# Main.net
KiCad netlist of a schematic drawn in Altium Designer
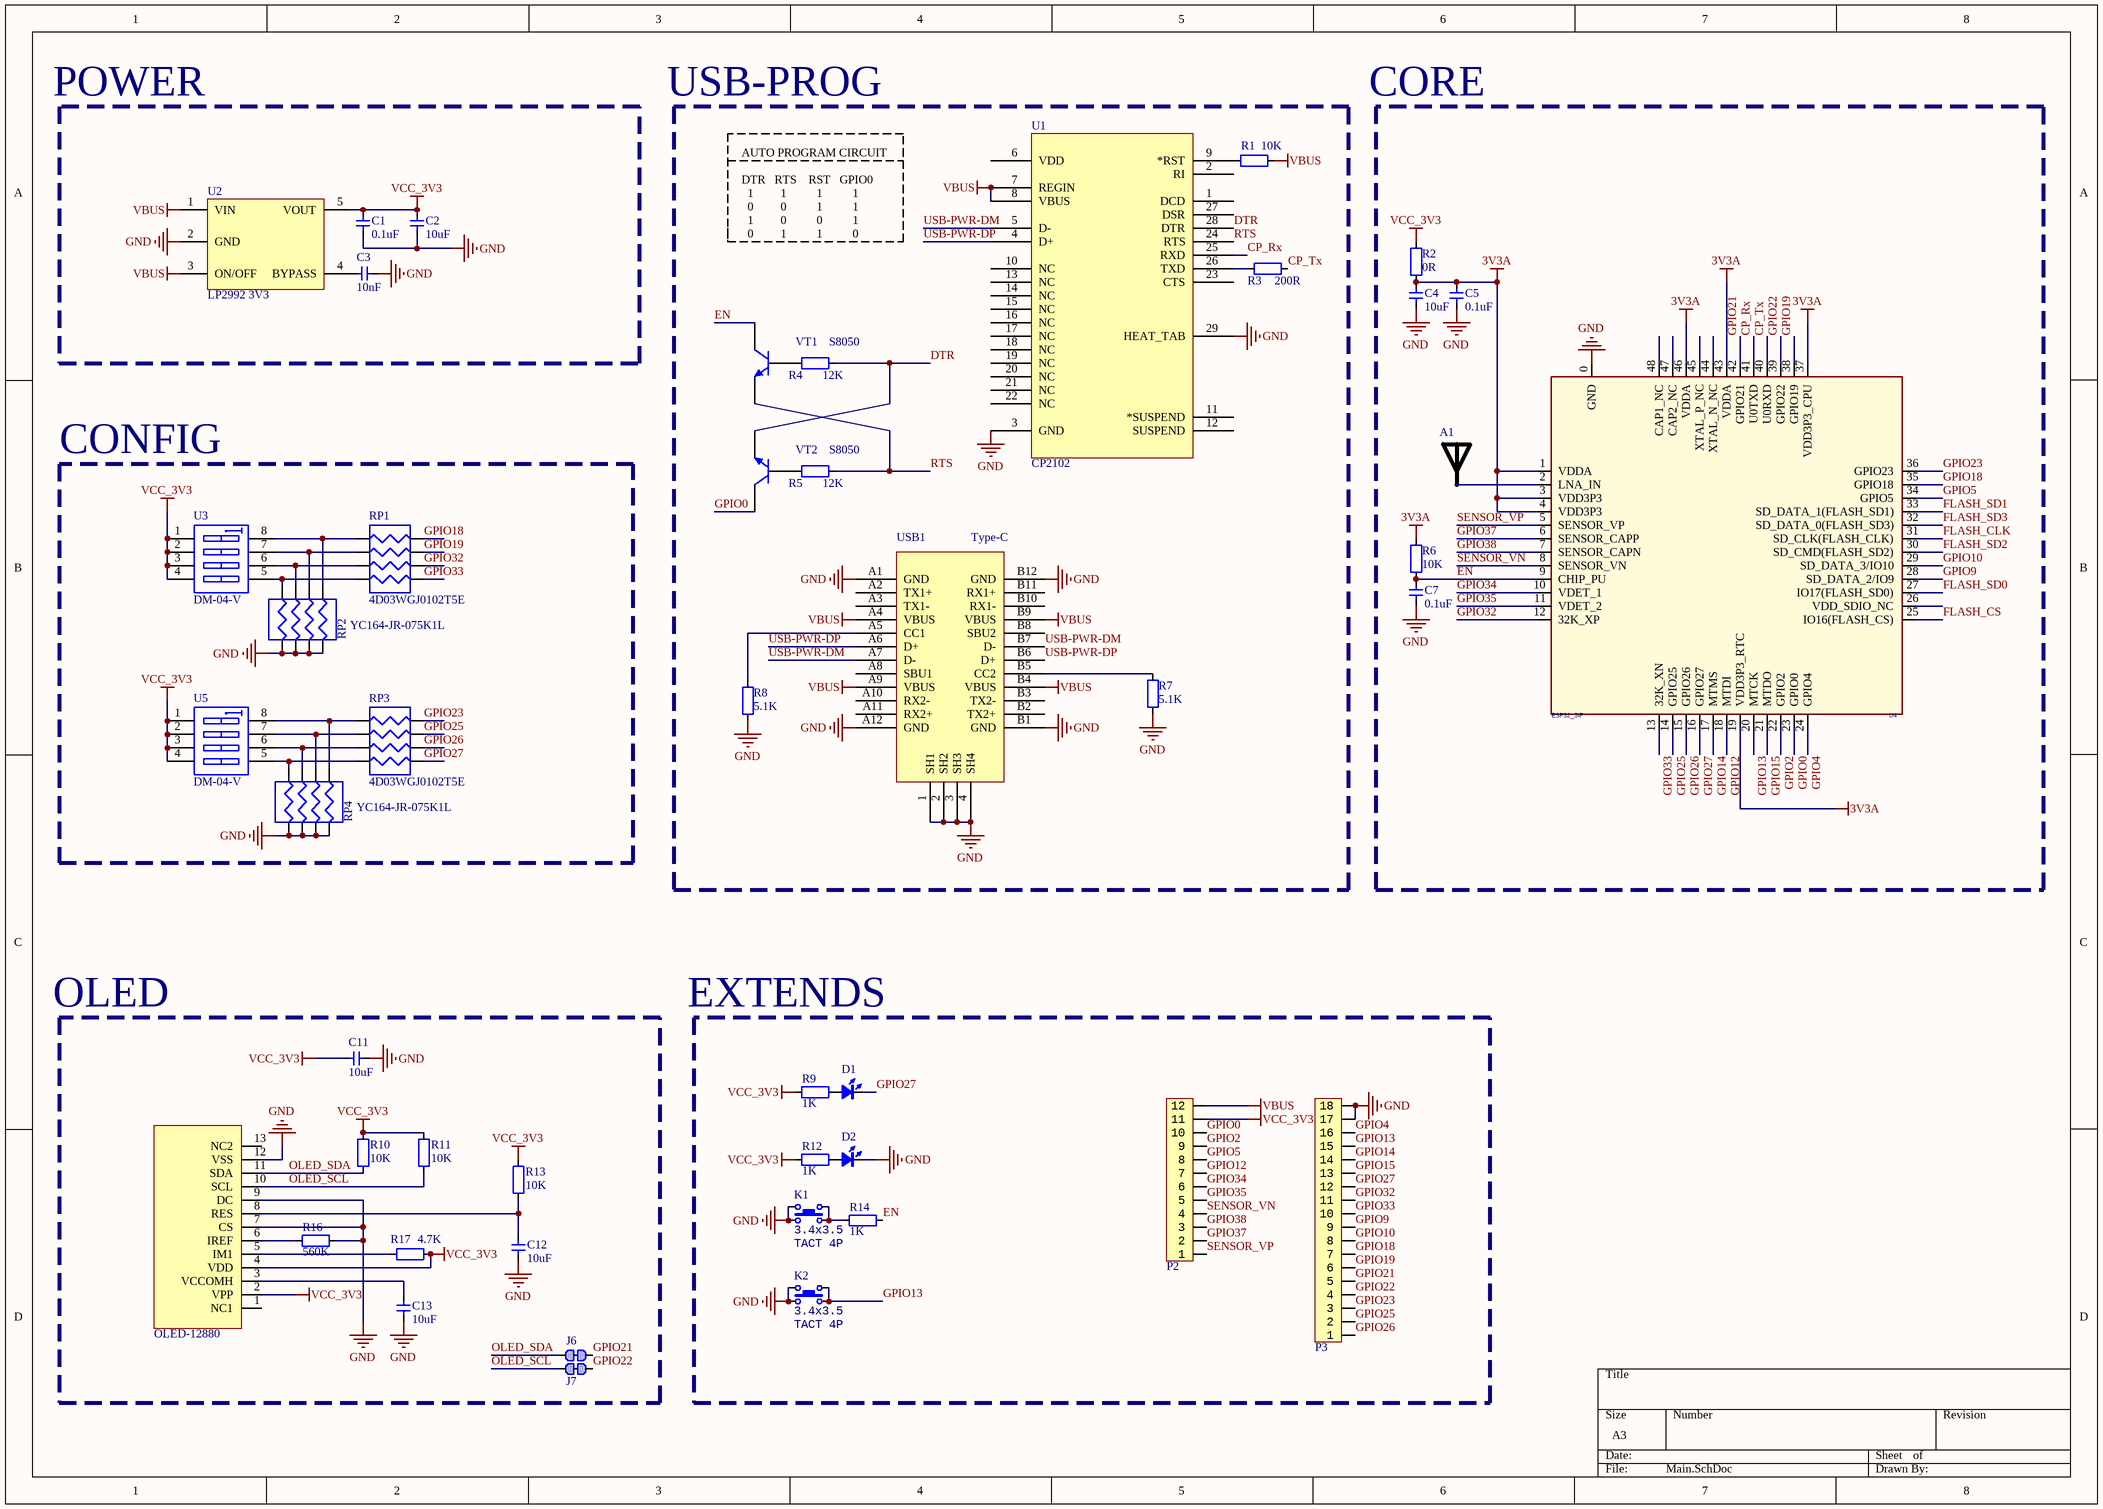
[diagram p0: Main.SchDoc]

(export (version "E")
  (design (tool "Eeschema 10.0.6"))
  (components
    (comp (ref "1")
      (value "OLED-12880")
      (footprint "OLED-12880")
      (libsource (lib "mLib") (part "OLED-12880"))
    )
    (comp (ref "A1")
      (value "RAINSUN")
      (footprint "ANT-Rainsun-AN5120")
      (libsource (lib "MyPcbLib") (part "ANT-Rainsun-AP5120"))
    )
    (comp (ref "C1")
      (value "0.1uF")
      (footprint "CAP_0402")
      (description "Capacitor")
      (libsource (lib "MyPcbLib") (part "电容-0402"))
    )
    (comp (ref "C2")
      (value "10uF")
      (footprint "CAP_0402")
      (description "Capacitor")
      (libsource (lib "MyPcbLib") (part "电容-0402"))
    )
    (comp (ref "C3")
      (value "10nF")
      (footprint "CAP_0402")
      (description "Capacitor")
      (libsource (lib "MyPcbLib") (part "电容-0402"))
    )
    (comp (ref "C4")
      (value "10uF")
      (footprint "CAP_0402")
      (description "Capacitor")
      (libsource (lib "MyPcbLib") (part "电容-0402"))
    )
    (comp (ref "C5")
      (value "0.1uF")
      (footprint "CAP_0402")
      (description "Capacitor")
      (libsource (lib "MyPcbLib") (part "电容-0402"))
    )
    (comp (ref "C7")
      (value "0.1uF")
      (footprint "CAP_0402")
      (description "Capacitor")
      (libsource (lib "MyPcbLib") (part "电容-0402"))
    )
    (comp (ref "C11")
      (value "10uF")
      (footprint "CAP_0402")
      (description "Capacitor")
      (libsource (lib "MyPcbLib") (part "电容-0402"))
    )
    (comp (ref "C12")
      (value "10uF")
      (footprint "CAP_0402")
      (description "Capacitor")
      (libsource (lib "MyPcbLib") (part "电容-0402"))
    )
    (comp (ref "C13")
      (value "10uF")
      (footprint "CAP_0402")
      (description "Capacitor")
      (libsource (lib "MyPcbLib") (part "电容-0402"))
    )
    (comp (ref "D1")
      (value "color?")
      (footprint "LED_0402_RED")
      (description "LED")
      (libsource (lib "KitSprout") (part "LED_0402"))
    )
    (comp (ref "D2")
      (value "color?")
      (footprint "LED_0402_RED")
      (description "LED")
      (libsource (lib "KitSprout") (part "LED_0402"))
    )
    (comp (ref "J6")
      (value "跳线")
      (footprint "0402-0R")
      (description "Resistor")
      (fields (field (name "PUBLISHER") "Altium Limited"))
      (libsource (lib "MyPcbLib") (part "跳线"))
    )
    (comp (ref "J7")
      (value "跳线")
      (footprint "0402-0R")
      (description "Resistor")
      (fields (field (name "PUBLISHER") "Altium Limited"))
      (libsource (lib "MyPcbLib") (part "跳线"))
    )
    (comp (ref "K1")
      (value "3.4x3.5")
      (footprint "ButtonTACT_3.5*3.55_90")
      (description "Button")
      (fields (field (name "TYPE") "TACT 4P") (field (name "Comment") "TACT 4P"))
      (libsource (lib "KitSprout") (part "ButtonTACT"))
    )
    (comp (ref "K2")
      (value "3.4x3.5")
      (footprint "ButtonTACT_3.5*3.55_90")
      (description "Button")
      (fields (field (name "TYPE") "TACT 4P") (field (name "Comment") "TACT 4P"))
      (libsource (lib "KitSprout") (part "ButtonTACT"))
    )
    (comp (ref "P2")
      (value "HDR1x12_2.54")
      (footprint "HDR1X12_2.54_180")
      (description "Header")
      (libsource (lib "KitSprout") (part "HDR1x12_2.54"))
    )
    (comp (ref "P3")
      (value "HDR1x18_2.54")
      (footprint "HDR1X18_2.54_180")
      (description "Header")
      (libsource (lib "KitSprout") (part "HDR1x18_2.54"))
    )
    (comp (ref "R1")
      (value "10K")
      (footprint "RES_0402")
      (description "Resistor")
      (libsource (lib "") (part "电阻-0402_2"))
    )
    (comp (ref "R2")
      (value "0R")
      (footprint "RES_0402")
      (description "Resistor")
      (libsource (lib "") (part "电阻-0402_1"))
    )
    (comp (ref "R3")
      (value "200R")
      (footprint "RES_0402")
      (description "Resistor")
      (libsource (lib "") (part "电阻-0402_2"))
    )
    (comp (ref "R4")
      (value "12K")
      (footprint "RES_0402")
      (description "Resistor")
      (libsource (lib "") (part "电阻-0402_2"))
    )
    (comp (ref "R5")
      (value "12K")
      (footprint "RES_0402")
      (description "Resistor")
      (libsource (lib "") (part "电阻-0402_2"))
    )
    (comp (ref "R6")
      (value "10K")
      (footprint "RES_0402")
      (description "Resistor")
      (libsource (lib "") (part "电阻-0402_1"))
    )
    (comp (ref "R7")
      (value "5.1K")
      (footprint "RES_0402")
      (description "Resistor")
      (libsource (lib "") (part "电阻-0402_1"))
    )
    (comp (ref "R8")
      (value "5.1K")
      (footprint "RES_0402")
      (description "Resistor")
      (libsource (lib "") (part "电阻-0402_1"))
    )
    (comp (ref "R9")
      (value "1K")
      (footprint "RES_0402")
      (description "Resistor")
      (libsource (lib "") (part "电阻-0402_3"))
    )
    (comp (ref "R10")
      (value "10K")
      (footprint "RES_0402")
      (description "Resistor")
      (libsource (lib "MyPcbLib") (part "电阻-0402"))
    )
    (comp (ref "R11")
      (value "10K")
      (footprint "RES_0402")
      (description "Resistor")
      (libsource (lib "MyPcbLib") (part "电阻-0402"))
    )
    (comp (ref "R12")
      (value "1K")
      (footprint "RES_0402")
      (description "Resistor")
      (libsource (lib "") (part "电阻-0402_3"))
    )
    (comp (ref "R13")
      (value "10K")
      (footprint "RES_0402")
      (description "Resistor")
      (libsource (lib "MyPcbLib") (part "电阻-0402"))
    )
    (comp (ref "R14")
      (value "1K")
      (footprint "RES_0402")
      (description "Resistor")
      (libsource (lib "") (part "电阻-0402_3"))
    )
    (comp (ref "R16")
      (value "560K")
      (footprint "RES_0402")
      (description "Resistor")
      (libsource (lib "") (part "电阻-0402_3"))
    )
    (comp (ref "R17")
      (value "4.7K")
      (footprint "RES_0402")
      (description "Resistor")
      (libsource (lib "") (part "电阻-0402_3"))
    )
    (comp (ref "RP1")
      (value "4D03WGJ0102T5E")
      (footprint "RES-ARRAY-SMD_0603-8P-L3.2-W1.6-BL")
      (libsource (lib "Schlib1") (part "RP"))
    )
    (comp (ref "RP2")
      (value "YC164-JR-075K1L")
      (footprint "RES-ARRAY-SMD_0603-8P-L3.2-W1.6-BL")
      (libsource (lib "Schlib1") (part "RP"))
    )
    (comp (ref "RP3")
      (value "4D03WGJ0102T5E")
      (footprint "RES-ARRAY-SMD_0603-8P-L3.2-W1.6-BL")
      (libsource (lib "Schlib1") (part "RP"))
    )
    (comp (ref "RP4")
      (value "YC164-JR-075K1L")
      (footprint "RES-ARRAY-SMD_0603-8P-L3.2-W1.6-BL")
      (libsource (lib "Schlib1") (part "RP"))
    )
    (comp (ref "U1")
      (value "CP2102")
      (footprint "QFN-28")
      (description "USB转TTL")
      (libsource (lib "mLib") (part "CP2102"))
    )
    (comp (ref "U2")
      (value "LP2992 3V3")
      (footprint "SOT23-5")
      (description "LDO")
      (libsource (lib "MyPcbLib") (part "LP2992"))
    )
    (comp (ref "U3")
      (value "DM-04-V")
      (footprint "SW-SMD_8P-L11.1-W6.2-P2.54-LS9.8")
      (description "DIP Switch, 4 Position, SPST")
      (fields (field (name "PUBLISHER") "Altium Limited"))
      (libsource (lib "Miscellaneous Devices") (part "SW DIP-4"))
    )
    (comp (ref "U4")
      (value "ESP32_SIP")
      (footprint "QFN-48_7X7")
      (libsource (lib "MyPcbLib") (part "ESP32-PICO"))
    )
    (comp (ref "U5")
      (value "DM-04-V")
      (footprint "SW-SMD_8P-L11.1-W6.2-P2.54-LS9.8")
      (description "DIP Switch, 4 Position, SPST")
      (fields (field (name "PUBLISHER") "Altium Limited"))
      (libsource (lib "Miscellaneous Devices") (part "SW DIP-4"))
    )
    (comp (ref "USB1")
      (value "Type-C")
      (footprint "Type-C-TOP")
      (libsource (lib "MyPcbLib") (part "USB-Type-C-TOP"))
    )
    (comp (ref "VT1")
      (value "S8050")
      (footprint "SMT_TRIODE_NPN")
      (description "Surface mount NPN transistor, package SOT-23")
      (libsource (lib "MyPcbLib") (part "SMT_TRIODE_NPN"))
    )
    (comp (ref "VT2")
      (value "S8050")
      (footprint "SMT_TRIODE_NPN")
      (description "Surface mount NPN transistor, package SOT-23")
      (libsource (lib "MyPcbLib") (part "SMT_TRIODE_NPN"))
    )
  )
  (nets
    (net (code "1") (name "/CP_Rx") (class "Default")
      (node (ref "U1") (pin "25") (pinfunction "RXD_25") (pintype "passive"))
      (node (ref "U4") (pin "41") (pinfunction "U0TXD_41") (pintype "power_in"))
    )
    (net (code "2") (name "/CP_Tx") (class "Default")
      (node (ref "R3") (pin "1") (pinfunction "1_1") (pintype "passive"))
      (node (ref "U4") (pin "40") (pinfunction "U0RXD_40") (pintype "power_in"))
    )
    (net (code "3") (name "/DTR") (class "Default")
      (node (ref "R4") (pin "1") (pinfunction "1_1") (pintype "passive"))
      (node (ref "U1") (pin "28") (pinfunction "DTR_28") (pintype "passive"))
      (node (ref "VT2") (pin "2") (pinfunction "E_2") (pintype "passive"))
    )
    (net (code "4") (name "/EN") (class "Default")
      (node (ref "C7") (pin "1") (pinfunction "1_1") (pintype "passive"))
      (node (ref "R14") (pin "2") (pinfunction "2_2") (pintype "passive"))
      (node (ref "R6") (pin "2") (pinfunction "2_2") (pintype "passive"))
      (node (ref "U4") (pin "9") (pinfunction "CHIP_PU_9") (pintype "passive"))
      (node (ref "VT1") (pin "3") (pinfunction "C_3") (pintype "passive"))
    )
    (net (code "5") (name "/FLASH_CLK") (class "Default")
      (node (ref "U4") (pin "31") (pinfunction "SD_CLK(FLASH_CLK)_31") (pintype "passive"))
    )
    (net (code "6") (name "/FLASH_CS") (class "Default")
      (node (ref "U4") (pin "25") (pinfunction "IO16(FLASH_CS)_25") (pintype "passive"))
    )
    (net (code "7") (name "/FLASH_SD0") (class "Default")
      (node (ref "U4") (pin "27") (pinfunction "IO17(FLASH_SD0)_27") (pintype "passive"))
    )
    (net (code "8") (name "/FLASH_SD1") (class "Default")
      (node (ref "U4") (pin "33") (pinfunction "SD_DATA_1(FLASH_SD1)_33") (pintype "passive"))
    )
    (net (code "9") (name "/FLASH_SD2") (class "Default")
      (node (ref "U4") (pin "30") (pinfunction "SD_CMD(FLASH_SD2)_30") (pintype "passive"))
    )
    (net (code "10") (name "/FLASH_SD3") (class "Default")
      (node (ref "U4") (pin "32") (pinfunction "SD_DATA_0(FLASH_SD3)_32") (pintype "passive"))
    )
    (net (code "11") (name "/GPIO0") (class "Default")
      (node (ref "P2") (pin "10") (pinfunction "10_10") (pintype "passive"))
      (node (ref "U4") (pin "23") (pinfunction "GPIO0_23") (pintype "passive"))
      (node (ref "VT2") (pin "3") (pinfunction "C_3") (pintype "passive"))
    )
    (net (code "12") (name "/GPIO2") (class "Default")
      (node (ref "P2") (pin "9") (pinfunction "9_9") (pintype "passive"))
      (node (ref "U4") (pin "22") (pinfunction "GPIO2_22") (pintype "passive"))
    )
    (net (code "13") (name "/GPIO4") (class "Default")
      (node (ref "P3") (pin "16") (pinfunction "16_16") (pintype "passive"))
      (node (ref "U4") (pin "24") (pinfunction "GPIO4_24") (pintype "passive"))
    )
    (net (code "14") (name "/GPIO5") (class "Default")
      (node (ref "P2") (pin "8") (pinfunction "8_8") (pintype "passive"))
      (node (ref "U4") (pin "34") (pinfunction "GPIO5_34") (pintype "passive"))
    )
    (net (code "15") (name "/GPIO9") (class "Default")
      (node (ref "P3") (pin "9") (pinfunction "9_9") (pintype "passive"))
      (node (ref "U4") (pin "28") (pinfunction "SD_DATA_2/IO9_28") (pintype "passive"))
    )
    (net (code "16") (name "/GPIO10") (class "Default")
      (node (ref "P3") (pin "8") (pinfunction "8_8") (pintype "passive"))
      (node (ref "U4") (pin "29") (pinfunction "SD_DATA_3/IO10_29") (pintype "passive"))
    )
    (net (code "17") (name "/GPIO12") (class "Default")
      (node (ref "P2") (pin "7") (pinfunction "7_7") (pintype "passive"))
      (node (ref "U4") (pin "18") (pinfunction "MTDI_18") (pintype "passive"))
    )
    (net (code "18") (name "/GPIO13") (class "Default")
      (node (ref "K2") (pin "2") (pinfunction "2_2") (pintype "passive"))
      (node (ref "K2") (pin "4") (pinfunction "4_4") (pintype "passive"))
      (node (ref "P3") (pin "15") (pinfunction "15_15") (pintype "passive"))
      (node (ref "U4") (pin "20") (pinfunction "MTCK_20") (pintype "passive"))
    )
    (net (code "19") (name "/GPIO14") (class "Default")
      (node (ref "P3") (pin "14") (pinfunction "14_14") (pintype "passive"))
      (node (ref "U4") (pin "17") (pinfunction "MTMS_17") (pintype "passive"))
    )
    (net (code "20") (name "/GPIO15") (class "Default")
      (node (ref "P3") (pin "13") (pinfunction "13_13") (pintype "passive"))
      (node (ref "U4") (pin "21") (pinfunction "MTDO_21") (pintype "passive"))
    )
    (net (code "21") (name "/GPIO18") (class "Default")
      (node (ref "P3") (pin "7") (pinfunction "7_7") (pintype "passive"))
      (node (ref "RP1") (pin "8") (pinfunction "8_8") (pintype "passive"))
      (node (ref "U4") (pin "35") (pinfunction "GPIO18_35") (pintype "passive"))
    )
    (net (code "22") (name "/GPIO19") (class "Default")
      (node (ref "P3") (pin "6") (pinfunction "6_6") (pintype "passive"))
      (node (ref "RP1") (pin "7") (pinfunction "7_7") (pintype "passive"))
      (node (ref "U4") (pin "38") (pinfunction "GPIO19_38") (pintype "passive"))
    )
    (net (code "23") (name "/GPIO21") (class "Default")
      (node (ref "J6") (pin "2") (pinfunction "2_2") (pintype "passive"))
      (node (ref "P3") (pin "5") (pinfunction "5_5") (pintype "passive"))
      (node (ref "U4") (pin "42") (pinfunction "GPIO21_42") (pintype "passive"))
    )
    (net (code "24") (name "/GPIO22") (class "Default")
      (node (ref "J7") (pin "2") (pinfunction "2_2") (pintype "passive"))
      (node (ref "P3") (pin "4") (pinfunction "4_4") (pintype "passive"))
      (node (ref "U4") (pin "39") (pinfunction "GPIO22_39") (pintype "passive"))
    )
    (net (code "25") (name "/GPIO23") (class "Default")
      (node (ref "P3") (pin "3") (pinfunction "3_3") (pintype "passive"))
      (node (ref "RP3") (pin "8") (pinfunction "8_8") (pintype "passive"))
      (node (ref "U4") (pin "36") (pinfunction "GPIO23_36") (pintype "passive"))
    )
    (net (code "26") (name "/GPIO25") (class "Default")
      (node (ref "P3") (pin "2") (pinfunction "2_2") (pintype "passive"))
      (node (ref "RP3") (pin "7") (pinfunction "7_7") (pintype "passive"))
      (node (ref "U4") (pin "14") (pinfunction "GPIO25_14") (pintype "passive"))
    )
    (net (code "27") (name "/GPIO26") (class "Default")
      (node (ref "P3") (pin "1") (pinfunction "1_1") (pintype "passive"))
      (node (ref "RP3") (pin "6") (pinfunction "6_6") (pintype "passive"))
      (node (ref "U4") (pin "15") (pinfunction "GPIO26_15") (pintype "passive"))
    )
    (net (code "28") (name "/GPIO27") (class "Default")
      (node (ref "D1") (pin "2") (pinfunction "K_2") (pintype "passive"))
      (node (ref "P3") (pin "12") (pinfunction "12_12") (pintype "passive"))
      (node (ref "RP3") (pin "5") (pinfunction "5_5") (pintype "passive"))
      (node (ref "U4") (pin "16") (pinfunction "GPIO27_16") (pintype "passive"))
    )
    (net (code "29") (name "/GPIO32") (class "Default")
      (node (ref "P3") (pin "11") (pinfunction "11_11") (pintype "passive"))
      (node (ref "RP1") (pin "6") (pinfunction "6_6") (pintype "passive"))
      (node (ref "U4") (pin "12") (pinfunction "32K_XP_12") (pintype "passive"))
    )
    (net (code "30") (name "/GPIO33") (class "Default")
      (node (ref "P3") (pin "10") (pinfunction "10_10") (pintype "passive"))
      (node (ref "RP1") (pin "5") (pinfunction "5_5") (pintype "passive"))
      (node (ref "U4") (pin "13") (pinfunction "32K_XN_13") (pintype "passive"))
    )
    (net (code "31") (name "/GPIO34") (class "Default")
      (node (ref "P2") (pin "6") (pinfunction "6_6") (pintype "passive"))
      (node (ref "U4") (pin "10") (pinfunction "VDET_1_10") (pintype "passive"))
    )
    (net (code "32") (name "/GPIO35") (class "Default")
      (node (ref "P2") (pin "5") (pinfunction "5_5") (pintype "passive"))
      (node (ref "U4") (pin "11") (pinfunction "VDET_2_11") (pintype "passive"))
    )
    (net (code "33") (name "/GPIO37") (class "Default")
      (node (ref "P2") (pin "2") (pinfunction "2_2") (pintype "passive"))
      (node (ref "U4") (pin "6") (pinfunction "SENSOR_CAPP_6") (pintype "passive"))
    )
    (net (code "34") (name "/GPIO38") (class "Default")
      (node (ref "P2") (pin "3") (pinfunction "3_3") (pintype "passive"))
      (node (ref "U4") (pin "7") (pinfunction "SENSOR_CAPN_7") (pintype "passive"))
    )
    (net (code "35") (name "/OLED_SCL") (class "Default")
      (node (ref "1") (pin "10") (pinfunction "SCL_10") (pintype "passive"))
      (node (ref "J7") (pin "1") (pinfunction "1_1") (pintype "passive"))
      (node (ref "R11") (pin "1") (pinfunction "1_1") (pintype "passive"))
    )
    (net (code "36") (name "/OLED_SDA") (class "Default")
      (node (ref "1") (pin "11") (pinfunction "SDA_11") (pintype "passive"))
      (node (ref "J6") (pin "1") (pinfunction "1_1") (pintype "passive"))
      (node (ref "R10") (pin "1") (pinfunction "1_1") (pintype "passive"))
    )
    (net (code "37") (name "/RTS") (class "Default")
      (node (ref "R5") (pin "1") (pinfunction "1_1") (pintype "passive"))
      (node (ref "U1") (pin "24") (pinfunction "RTS_24") (pintype "passive"))
      (node (ref "VT1") (pin "2") (pinfunction "E_2") (pintype "passive"))
    )
    (net (code "38") (name "/SENSOR_VN") (class "Default")
      (node (ref "P2") (pin "4") (pinfunction "4_4") (pintype "passive"))
      (node (ref "U4") (pin "8") (pinfunction "SENSOR_VN_8") (pintype "passive"))
    )
    (net (code "39") (name "/SENSOR_VP") (class "Default")
      (node (ref "P2") (pin "1") (pinfunction "1_1") (pintype "passive"))
      (node (ref "U4") (pin "5") (pinfunction "SENSOR_VP_5") (pintype "passive"))
    )
    (net (code "40") (name "/USB-PWR-DM") (class "Default")
      (node (ref "U1") (pin "5") (pinfunction "D-_5") (pintype "passive"))
      (node (ref "USB1") (pin "A7") (pinfunction "D-_A7") (pintype "passive"))
      (node (ref "USB1") (pin "B7") (pinfunction "D-_B7") (pintype "passive"))
    )
    (net (code "41") (name "/USB-PWR-DP") (class "Default")
      (node (ref "U1") (pin "4") (pinfunction "D+_4") (pintype "passive"))
      (node (ref "USB1") (pin "A6") (pinfunction "D+_A6") (pintype "passive"))
      (node (ref "USB1") (pin "B6") (pinfunction "D+_B6") (pintype "passive"))
    )
    (net (code "42") (name "3V3A") (class "Default")
      (node (ref "C4") (pin "2") (pinfunction "2_2") (pintype "passive"))
      (node (ref "C5") (pin "2") (pinfunction "2_2") (pintype "passive"))
      (node (ref "R2") (pin "2") (pinfunction "2_2") (pintype "passive"))
      (node (ref "R6") (pin "1") (pinfunction "1_1") (pintype "passive"))
      (node (ref "U4") (pin "1") (pinfunction "VDDA_1") (pintype "power_in"))
      (node (ref "U4") (pin "19") (pinfunction "VDD3P3_RTC_19") (pintype "power_in"))
      (node (ref "U4") (pin "3") (pinfunction "VDD3P3_3") (pintype "power_in"))
      (node (ref "U4") (pin "37") (pinfunction "VDD3P3_CPU_37") (pintype "power_in"))
      (node (ref "U4") (pin "4") (pinfunction "VDD3P3_4") (pintype "power_in"))
      (node (ref "U4") (pin "43") (pinfunction "VDDA_43") (pintype "power_in"))
      (node (ref "U4") (pin "46") (pinfunction "VDDA_46") (pintype "power_in"))
    )
    (net (code "43") (name "GND") (class "Default")
      (node (ref "1") (pin "12") (pinfunction "VSS_12") (pintype "passive"))
      (node (ref "1") (pin "7") (pinfunction "CS_7") (pintype "passive"))
      (node (ref "1") (pin "9") (pinfunction "DC_9") (pintype "passive"))
      (node (ref "C1") (pin "1") (pinfunction "1_1") (pintype "passive"))
      (node (ref "C11") (pin "1") (pinfunction "1_1") (pintype "passive"))
      (node (ref "C12") (pin "1") (pinfunction "1_1") (pintype "passive"))
      (node (ref "C13") (pin "1") (pinfunction "1_1") (pintype "passive"))
      (node (ref "C2") (pin "1") (pinfunction "1_1") (pintype "passive"))
      (node (ref "C3") (pin "1") (pinfunction "1_1") (pintype "passive"))
      (node (ref "C4") (pin "1") (pinfunction "1_1") (pintype "passive"))
      (node (ref "C5") (pin "1") (pinfunction "1_1") (pintype "passive"))
      (node (ref "C7") (pin "2") (pinfunction "2_2") (pintype "passive"))
      (node (ref "D2") (pin "2") (pinfunction "K_2") (pintype "passive"))
      (node (ref "K1") (pin "1") (pinfunction "1_1") (pintype "passive"))
      (node (ref "K1") (pin "3") (pinfunction "3_3") (pintype "passive"))
      (node (ref "K2") (pin "1") (pinfunction "1_1") (pintype "passive"))
      (node (ref "K2") (pin "3") (pinfunction "3_3") (pintype "passive"))
      (node (ref "P3") (pin "17") (pinfunction "17_17") (pintype "passive"))
      (node (ref "P3") (pin "18") (pinfunction "18_18") (pintype "passive"))
      (node (ref "R16") (pin "2") (pinfunction "2_2") (pintype "passive"))
      (node (ref "R7") (pin "2") (pinfunction "2_2") (pintype "passive"))
      (node (ref "R8") (pin "2") (pinfunction "2_2") (pintype "passive"))
      (node (ref "RP2") (pin "5") (pinfunction "5_5") (pintype "passive"))
      (node (ref "RP2") (pin "6") (pinfunction "6_6") (pintype "passive"))
      (node (ref "RP2") (pin "7") (pinfunction "7_7") (pintype "passive"))
      (node (ref "RP2") (pin "8") (pinfunction "8_8") (pintype "passive"))
      (node (ref "RP4") (pin "5") (pinfunction "5_5") (pintype "passive"))
      (node (ref "RP4") (pin "6") (pinfunction "6_6") (pintype "passive"))
      (node (ref "RP4") (pin "7") (pinfunction "7_7") (pintype "passive"))
      (node (ref "RP4") (pin "8") (pinfunction "8_8") (pintype "passive"))
      (node (ref "U1") (pin "29") (pinfunction "HEAT_TAB_29") (pintype "passive"))
      (node (ref "U1") (pin "3") (pinfunction "GND_3") (pintype "passive"))
      (node (ref "U2") (pin "2") (pinfunction "GND_2") (pintype "passive"))
      (node (ref "U4") (pin "0") (pinfunction "GND_0") (pintype "power_in"))
      (node (ref "USB1") (pin "1") (pinfunction "SH1_1") (pintype "passive"))
      (node (ref "USB1") (pin "2") (pinfunction "SH2_2") (pintype "passive"))
      (node (ref "USB1") (pin "3") (pinfunction "SH3_3") (pintype "passive"))
      (node (ref "USB1") (pin "4") (pinfunction "SH4_4") (pintype "passive"))
      (node (ref "USB1") (pin "A1") (pinfunction "GND_A1") (pintype "passive"))
      (node (ref "USB1") (pin "A12") (pinfunction "GND_A12") (pintype "passive"))
      (node (ref "USB1") (pin "B1") (pinfunction "GND_B1") (pintype "passive"))
      (node (ref "USB1") (pin "B12") (pinfunction "GND_B12") (pintype "passive"))
    )
    (net (code "44") (name "Net-(1-IM1)") (class "Default")
      (node (ref "1") (pin "5") (pinfunction "IM1_5") (pintype "passive"))
      (node (ref "R17") (pin "1") (pinfunction "1_1") (pintype "passive"))
    )
    (net (code "45") (name "Net-(1-IREF)") (class "Default")
      (node (ref "1") (pin "6") (pinfunction "IREF_6") (pintype "passive"))
      (node (ref "R16") (pin "1") (pinfunction "1_1") (pintype "passive"))
    )
    (net (code "46") (name "Net-(1-RES)") (class "Default")
      (node (ref "1") (pin "8") (pinfunction "RES_8") (pintype "passive"))
      (node (ref "C12") (pin "2") (pinfunction "2_2") (pintype "passive"))
      (node (ref "R13") (pin "1") (pinfunction "1_1") (pintype "passive"))
    )
    (net (code "47") (name "Net-(1-VCCOMH)") (class "Default")
      (node (ref "1") (pin "3") (pinfunction "VCCOMH_3") (pintype "passive"))
      (node (ref "C13") (pin "2") (pinfunction "2_2") (pintype "passive"))
    )
    (net (code "48") (name "Net-(D1-A)") (class "Default")
      (node (ref "D1") (pin "1") (pinfunction "A_1") (pintype "passive"))
      (node (ref "R9") (pin "2") (pinfunction "2_2") (pintype "passive"))
    )
    (net (code "49") (name "Net-(D2-A)") (class "Default")
      (node (ref "D2") (pin "1") (pinfunction "A_1") (pintype "passive"))
      (node (ref "R12") (pin "2") (pinfunction "2_2") (pintype "passive"))
    )
    (net (code "50") (name "Net-(K1-Pad2)") (class "Default")
      (node (ref "K1") (pin "2") (pinfunction "2_2") (pintype "passive"))
      (node (ref "K1") (pin "4") (pinfunction "4_4") (pintype "passive"))
      (node (ref "R14") (pin "1") (pinfunction "1_1") (pintype "passive"))
    )
    (net (code "51") (name "Net-(U1-*RST)") (class "Default")
      (node (ref "R1") (pin "2") (pinfunction "2_2") (pintype "passive"))
      (node (ref "U1") (pin "9") (pinfunction "*RST_9") (pintype "passive"))
    )
    (net (code "52") (name "Net-(U1-TXD)") (class "Default")
      (node (ref "R3") (pin "2") (pinfunction "2_2") (pintype "passive"))
      (node (ref "U1") (pin "26") (pinfunction "TXD_26") (pintype "passive"))
    )
    (net (code "53") (name "Net-(U2-BYPASS)") (class "Default")
      (node (ref "C3") (pin "2") (pinfunction "2_2") (pintype "passive"))
      (node (ref "U2") (pin "4") (pinfunction "BYPASS_4") (pintype "passive"))
    )
    (net (code "54") (name "Net-(U3-B1)") (class "Default")
      (node (ref "RP1") (pin "1") (pinfunction "1_1") (pintype "passive"))
      (node (ref "RP2") (pin "1") (pinfunction "1_1") (pintype "passive"))
      (node (ref "U3") (pin "8") (pinfunction "B1_8") (pintype "passive"))
    )
    (net (code "55") (name "Net-(U3-B2)") (class "Default")
      (node (ref "RP1") (pin "2") (pinfunction "2_2") (pintype "passive"))
      (node (ref "RP2") (pin "2") (pinfunction "2_2") (pintype "passive"))
      (node (ref "U3") (pin "7") (pinfunction "B2_7") (pintype "passive"))
    )
    (net (code "56") (name "Net-(U3-B3)") (class "Default")
      (node (ref "RP1") (pin "3") (pinfunction "3_3") (pintype "passive"))
      (node (ref "RP2") (pin "3") (pinfunction "3_3") (pintype "passive"))
      (node (ref "U3") (pin "6") (pinfunction "B3_6") (pintype "passive"))
    )
    (net (code "57") (name "Net-(U3-B4)") (class "Default")
      (node (ref "RP1") (pin "4") (pinfunction "4_4") (pintype "passive"))
      (node (ref "RP2") (pin "4") (pinfunction "4_4") (pintype "passive"))
      (node (ref "U3") (pin "5") (pinfunction "B4_5") (pintype "passive"))
    )
    (net (code "58") (name "Net-(U4-LNA_IN)") (class "Default")
      (node (ref "A1") (pin "1") (pinfunction "1_1") (pintype "passive"))
      (node (ref "U4") (pin "2") (pinfunction "LNA_IN_2") (pintype "passive"))
    )
    (net (code "59") (name "Net-(U5-B1)") (class "Default")
      (node (ref "RP3") (pin "1") (pinfunction "1_1") (pintype "passive"))
      (node (ref "RP4") (pin "1") (pinfunction "1_1") (pintype "passive"))
      (node (ref "U5") (pin "8") (pinfunction "B1_8") (pintype "passive"))
    )
    (net (code "60") (name "Net-(U5-B2)") (class "Default")
      (node (ref "RP3") (pin "2") (pinfunction "2_2") (pintype "passive"))
      (node (ref "RP4") (pin "2") (pinfunction "2_2") (pintype "passive"))
      (node (ref "U5") (pin "7") (pinfunction "B2_7") (pintype "passive"))
    )
    (net (code "61") (name "Net-(U5-B3)") (class "Default")
      (node (ref "RP3") (pin "3") (pinfunction "3_3") (pintype "passive"))
      (node (ref "RP4") (pin "3") (pinfunction "3_3") (pintype "passive"))
      (node (ref "U5") (pin "6") (pinfunction "B3_6") (pintype "passive"))
    )
    (net (code "62") (name "Net-(U5-B4)") (class "Default")
      (node (ref "RP3") (pin "4") (pinfunction "4_4") (pintype "passive"))
      (node (ref "RP4") (pin "4") (pinfunction "4_4") (pintype "passive"))
      (node (ref "U5") (pin "5") (pinfunction "B4_5") (pintype "passive"))
    )
    (net (code "63") (name "Net-(USB1-CC1)") (class "Default")
      (node (ref "R8") (pin "1") (pinfunction "1_1") (pintype "passive"))
      (node (ref "USB1") (pin "A5") (pinfunction "CC1_A5") (pintype "passive"))
    )
    (net (code "64") (name "Net-(USB1-CC2)") (class "Default")
      (node (ref "R7") (pin "1") (pinfunction "1_1") (pintype "passive"))
      (node (ref "USB1") (pin "B5") (pinfunction "CC2_B5") (pintype "passive"))
    )
    (net (code "65") (name "Net-(VT1-B)") (class "Default")
      (node (ref "R4") (pin "2") (pinfunction "2_2") (pintype "passive"))
      (node (ref "VT1") (pin "1") (pinfunction "B_1") (pintype "passive"))
    )
    (net (code "66") (name "Net-(VT2-B)") (class "Default")
      (node (ref "R5") (pin "2") (pinfunction "2_2") (pintype "passive"))
      (node (ref "VT2") (pin "1") (pinfunction "B_1") (pintype "passive"))
    )
    (net (code "67") (name "VBUS") (class "Default")
      (node (ref "P2") (pin "12") (pinfunction "12_12") (pintype "passive"))
      (node (ref "R1") (pin "1") (pinfunction "1_1") (pintype "passive"))
      (node (ref "U1") (pin "7") (pinfunction "REGIN_7") (pintype "passive"))
      (node (ref "U1") (pin "8") (pinfunction "VBUS_8") (pintype "passive"))
      (node (ref "U2") (pin "1") (pinfunction "VIN_1") (pintype "passive"))
      (node (ref "U2") (pin "3") (pinfunction "ON/OFF_3") (pintype "passive"))
      (node (ref "USB1") (pin "A4") (pinfunction "VBUS_A4") (pintype "passive"))
      (node (ref "USB1") (pin "A9") (pinfunction "VBUS_A9") (pintype "passive"))
      (node (ref "USB1") (pin "B4") (pinfunction "VBUS_B4") (pintype "passive"))
      (node (ref "USB1") (pin "B9") (pinfunction "VBUS_B9") (pintype "passive"))
    )
    (net (code "68") (name "VCC_3V3") (class "Default")
      (node (ref "1") (pin "2") (pinfunction "VPP_2") (pintype "passive"))
      (node (ref "1") (pin "4") (pinfunction "VDD_4") (pintype "passive"))
      (node (ref "C1") (pin "2") (pinfunction "2_2") (pintype "passive"))
      (node (ref "C11") (pin "2") (pinfunction "2_2") (pintype "passive"))
      (node (ref "C2") (pin "2") (pinfunction "2_2") (pintype "passive"))
      (node (ref "P2") (pin "11") (pinfunction "11_11") (pintype "passive"))
      (node (ref "R10") (pin "2") (pinfunction "2_2") (pintype "passive"))
      (node (ref "R11") (pin "2") (pinfunction "2_2") (pintype "passive"))
      (node (ref "R12") (pin "1") (pinfunction "1_1") (pintype "passive"))
      (node (ref "R13") (pin "2") (pinfunction "2_2") (pintype "passive"))
      (node (ref "R17") (pin "2") (pinfunction "2_2") (pintype "passive"))
      (node (ref "R2") (pin "1") (pinfunction "1_1") (pintype "passive"))
      (node (ref "R9") (pin "1") (pinfunction "1_1") (pintype "passive"))
      (node (ref "U2") (pin "5") (pinfunction "VOUT_5") (pintype "passive"))
      (node (ref "U3") (pin "1") (pinfunction "A1_1") (pintype "passive"))
      (node (ref "U3") (pin "2") (pinfunction "A2_2") (pintype "passive"))
      (node (ref "U3") (pin "3") (pinfunction "A3_3") (pintype "passive"))
      (node (ref "U3") (pin "4") (pinfunction "A4_4") (pintype "passive"))
      (node (ref "U5") (pin "1") (pinfunction "A1_1") (pintype "passive"))
      (node (ref "U5") (pin "2") (pinfunction "A2_2") (pintype "passive"))
      (node (ref "U5") (pin "3") (pinfunction "A3_3") (pintype "passive"))
      (node (ref "U5") (pin "4") (pinfunction "A4_4") (pintype "passive"))
    )
    (net (code "69") (name "unconnected-(1-NC1-Pad1)") (class "Default")
      (node (ref "1") (pin "1") (pinfunction "NC1_1") (pintype "passive"))
    )
    (net (code "70") (name "unconnected-(1-NC2-Pad13)") (class "Default")
      (node (ref "1") (pin "13") (pinfunction "NC2_13") (pintype "passive"))
    )
    (net (code "71") (name "unconnected-(U1-*SUSPEND-Pad11)") (class "Default")
      (node (ref "U1") (pin "11") (pinfunction "*SUSPEND_11") (pintype "passive"))
    )
    (net (code "72") (name "unconnected-(U1-CTS-Pad23)") (class "Default")
      (node (ref "U1") (pin "23") (pinfunction "CTS_23") (pintype "passive"))
    )
    (net (code "73") (name "unconnected-(U1-DCD-Pad1)") (class "Default")
      (node (ref "U1") (pin "1") (pinfunction "DCD_1") (pintype "passive"))
    )
    (net (code "74") (name "unconnected-(U1-DSR-Pad27)") (class "Default")
      (node (ref "U1") (pin "27") (pinfunction "DSR_27") (pintype "passive"))
    )
    (net (code "75") (name "unconnected-(U1-NC-Pad10)") (class "Default")
      (node (ref "U1") (pin "10") (pinfunction "NC_10") (pintype "passive"))
    )
    (net (code "76") (name "unconnected-(U1-NC-Pad13)") (class "Default")
      (node (ref "U1") (pin "13") (pinfunction "NC_13") (pintype "passive"))
    )
    (net (code "77") (name "unconnected-(U1-NC-Pad14)") (class "Default")
      (node (ref "U1") (pin "14") (pinfunction "NC_14") (pintype "passive"))
    )
    (net (code "78") (name "unconnected-(U1-NC-Pad15)") (class "Default")
      (node (ref "U1") (pin "15") (pinfunction "NC_15") (pintype "passive"))
    )
    (net (code "79") (name "unconnected-(U1-NC-Pad16)") (class "Default")
      (node (ref "U1") (pin "16") (pinfunction "NC_16") (pintype "passive"))
    )
    (net (code "80") (name "unconnected-(U1-NC-Pad17)") (class "Default")
      (node (ref "U1") (pin "17") (pinfunction "NC_17") (pintype "passive"))
    )
    (net (code "81") (name "unconnected-(U1-NC-Pad18)") (class "Default")
      (node (ref "U1") (pin "18") (pinfunction "NC_18") (pintype "passive"))
    )
    (net (code "82") (name "unconnected-(U1-NC-Pad19)") (class "Default")
      (node (ref "U1") (pin "19") (pinfunction "NC_19") (pintype "passive"))
    )
    (net (code "83") (name "unconnected-(U1-NC-Pad20)") (class "Default")
      (node (ref "U1") (pin "20") (pinfunction "NC_20") (pintype "passive"))
    )
    (net (code "84") (name "unconnected-(U1-NC-Pad21)") (class "Default")
      (node (ref "U1") (pin "21") (pinfunction "NC_21") (pintype "passive"))
    )
    (net (code "85") (name "unconnected-(U1-NC-Pad22)") (class "Default")
      (node (ref "U1") (pin "22") (pinfunction "NC_22") (pintype "passive"))
    )
    (net (code "86") (name "unconnected-(U1-RI-Pad2)") (class "Default")
      (node (ref "U1") (pin "2") (pinfunction "RI_2") (pintype "passive"))
    )
    (net (code "87") (name "unconnected-(U1-SUSPEND-Pad12)") (class "Default")
      (node (ref "U1") (pin "12") (pinfunction "SUSPEND_12") (pintype "passive"))
    )
    (net (code "88") (name "unconnected-(U1-VDD-Pad6)") (class "Default")
      (node (ref "U1") (pin "6") (pinfunction "VDD_6") (pintype "passive"))
    )
    (net (code "89") (name "unconnected-(U4-CAP1_NC-Pad48)") (class "Default")
      (node (ref "U4") (pin "48") (pinfunction "CAP1_NC_48") (pintype "passive"))
    )
    (net (code "90") (name "unconnected-(U4-CAP2_NC-Pad47)") (class "Default")
      (node (ref "U4") (pin "47") (pinfunction "CAP2_NC_47") (pintype "passive"))
    )
    (net (code "91") (name "unconnected-(U4-VDD_SDIO_NC-Pad26)") (class "Default")
      (node (ref "U4") (pin "26") (pinfunction "VDD_SDIO_NC_26") (pintype "passive"))
    )
    (net (code "92") (name "unconnected-(U4-XTAL_N_NC-Pad44)") (class "Default")
      (node (ref "U4") (pin "44") (pinfunction "XTAL_N_NC_44") (pintype "passive"))
    )
    (net (code "93") (name "unconnected-(U4-XTAL_P_NC-Pad45)") (class "Default")
      (node (ref "U4") (pin "45") (pinfunction "XTAL_P_NC_45") (pintype "passive"))
    )
    (net (code "94") (name "unconnected-(USB1-RX1+-PadB11)") (class "Default")
      (node (ref "USB1") (pin "B11") (pinfunction "RX1+_B11") (pintype "passive"))
    )
    (net (code "95") (name "unconnected-(USB1-RX1--PadB10)") (class "Default")
      (node (ref "USB1") (pin "B10") (pinfunction "RX1-_B10") (pintype "passive"))
    )
    (net (code "96") (name "unconnected-(USB1-RX2+-PadA11)") (class "Default")
      (node (ref "USB1") (pin "A11") (pinfunction "RX2+_A11") (pintype "passive"))
    )
    (net (code "97") (name "unconnected-(USB1-RX2--PadA10)") (class "Default")
      (node (ref "USB1") (pin "A10") (pinfunction "RX2-_A10") (pintype "passive"))
    )
    (net (code "98") (name "unconnected-(USB1-SBU1-PadA8)") (class "Default")
      (node (ref "USB1") (pin "A8") (pinfunction "SBU1_A8") (pintype "passive"))
    )
    (net (code "99") (name "unconnected-(USB1-SBU2-PadB8)") (class "Default")
      (node (ref "USB1") (pin "B8") (pinfunction "SBU2_B8") (pintype "passive"))
    )
    (net (code "100") (name "unconnected-(USB1-TX1+-PadA2)") (class "Default")
      (node (ref "USB1") (pin "A2") (pinfunction "TX1+_A2") (pintype "passive"))
    )
    (net (code "101") (name "unconnected-(USB1-TX1--PadA3)") (class "Default")
      (node (ref "USB1") (pin "A3") (pinfunction "TX1-_A3") (pintype "passive"))
    )
    (net (code "102") (name "unconnected-(USB1-TX2+-PadB2)") (class "Default")
      (node (ref "USB1") (pin "B2") (pinfunction "TX2+_B2") (pintype "passive"))
    )
    (net (code "103") (name "unconnected-(USB1-TX2--PadB3)") (class "Default")
      (node (ref "USB1") (pin "B3") (pinfunction "TX2-_B3") (pintype "passive"))
    )
  )
)
